# Power_1.net
KiCad netlist of a schematic drawn in Altium Designer
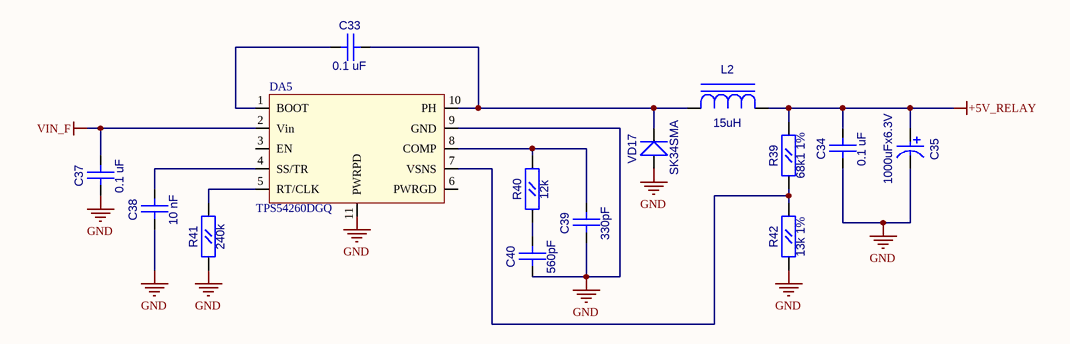
[diagram p0: Power_1.SchDoc]

(export (version "E")
  (design (tool "Eeschema 10.0.6"))
  (components
    (comp (ref "C33")
      (value "0.1 uF")
      (footprint "CC0603")
      (description "CC0603")
      (libsource (lib "gprs_modem_2") (part "CC0603"))
    )
    (comp (ref "C34")
      (value "0.1 uF")
      (footprint "CC0603")
      (description "CC0603")
      (libsource (lib "gprs_modem_2") (part "CC0603"))
    )
    (comp (ref "C35")
      (value "1000uFx6.3V")
      (footprint "CC8X3.5")
      (description "CAP0.35")
      (libsource (lib "gprs_modem_2") (part "CAP0.35"))
    )
    (comp (ref "C37")
      (value "0.1 uF")
      (footprint "CC0603")
      (description "CC0603")
      (libsource (lib "gprs_modem_2") (part "CC0603"))
    )
    (comp (ref "C38")
      (value "10 nF")
      (footprint "CC0603")
      (description "CC0603")
      (libsource (lib "gprs_modem_2") (part "CC0603"))
    )
    (comp (ref "C39")
      (value "330pF")
      (footprint "CC0603")
      (description "CC0603")
      (libsource (lib "gprs_modem_2") (part "CC0603"))
    )
    (comp (ref "C40")
      (value "560pF")
      (footprint "CC0603")
      (description "CC0603")
      (libsource (lib "gprs_modem_2") (part "CC0603"))
    )
    (comp (ref "DA5")
      (value "TPS54260DGQ")
      (footprint "S-PDSO-G10")
      (libsource (lib "gprs_modem_2") (part "TPS54260DGQ"))
    )
    (comp (ref "L2")
      (value "15uH")
      (footprint "SDR0805")
      (description "SDR0805")
      (libsource (lib "gprs_modem_2") (part "SDR0805"))
    )
    (comp (ref "R39")
      (value "68k1 1%")
      (footprint "RC0603")
      (description "RC0603")
      (libsource (lib "gprs_modem_2") (part "RC0603"))
    )
    (comp (ref "R40")
      (value "12k")
      (footprint "RC0603")
      (description "RC0603")
      (libsource (lib "gprs_modem_2") (part "RC0603"))
    )
    (comp (ref "R41")
      (value "240k")
      (footprint "RC0603")
      (description "RC0603")
      (libsource (lib "gprs_modem_2") (part "RC0603"))
    )
    (comp (ref "R42")
      (value "13k 1%")
      (footprint "RC0603")
      (description "RC0603")
      (libsource (lib "gprs_modem_2") (part "RC0603"))
    )
    (comp (ref "VD17")
      (value "SK34SMA")
      (footprint "SMA")
      (description "Schottky Rectifier")
      (libsource (lib "gprs_modem") (part "SK34SMA"))
    )
  )
  (nets
    (net (code "1") (name "+5V_RELAY") (class "Default")
      (node (ref "C34") (pin "1") (pinfunction "A_1") (pintype "passive"))
      (node (ref "C35") (pin "1") (pintype "passive"))
      (node (ref "L2") (pin "2") (pinfunction "A_2") (pintype "passive"))
      (node (ref "R39") (pin "2") (pinfunction "B_2") (pintype "passive"))
    )
    (net (code "2") (name "GND") (class "Default")
      (node (ref "C34") (pin "2") (pinfunction "B_2") (pintype "passive"))
      (node (ref "C35") (pin "2") (pintype "passive"))
      (node (ref "C37") (pin "2") (pinfunction "B_2") (pintype "passive"))
      (node (ref "C38") (pin "2") (pinfunction "B_2") (pintype "passive"))
      (node (ref "C39") (pin "2") (pinfunction "B_2") (pintype "passive"))
      (node (ref "C40") (pin "2") (pinfunction "B_2") (pintype "passive"))
      (node (ref "DA5") (pin "11") (pinfunction "PWRPD_11") (pintype "passive"))
      (node (ref "DA5") (pin "9") (pinfunction "GND_9") (pintype "passive"))
      (node (ref "R41") (pin "1") (pinfunction "A_1") (pintype "passive"))
      (node (ref "R42") (pin "1") (pinfunction "A_1") (pintype "passive"))
      (node (ref "VD17") (pin "1") (pinfunction "A_1") (pintype "passive"))
    )
    (net (code "3") (name "Net-(C33-A)") (class "Default")
      (node (ref "C33") (pin "1") (pinfunction "A_1") (pintype "passive"))
      (node (ref "DA5") (pin "10") (pinfunction "PH_10") (pintype "passive"))
      (node (ref "L2") (pin "1") (pinfunction "C_1") (pintype "passive"))
      (node (ref "VD17") (pin "2") (pinfunction "K_2") (pintype "passive"))
    )
    (net (code "4") (name "Net-(C33-B)") (class "Default")
      (node (ref "C33") (pin "2") (pinfunction "B_2") (pintype "passive"))
      (node (ref "DA5") (pin "1") (pinfunction "BOOT_1") (pintype "passive"))
    )
    (net (code "5") (name "Net-(C38-A)") (class "Default")
      (node (ref "C38") (pin "1") (pinfunction "A_1") (pintype "passive"))
      (node (ref "DA5") (pin "4") (pinfunction "SS/TR_4") (pintype "passive"))
    )
    (net (code "6") (name "Net-(C39-A)") (class "Default")
      (node (ref "C39") (pin "1") (pinfunction "A_1") (pintype "passive"))
      (node (ref "DA5") (pin "8") (pinfunction "COMP_8") (pintype "passive"))
      (node (ref "R40") (pin "2") (pinfunction "B_2") (pintype "passive"))
    )
    (net (code "7") (name "Net-(C40-A)") (class "Default")
      (node (ref "C40") (pin "1") (pinfunction "A_1") (pintype "passive"))
      (node (ref "R40") (pin "1") (pinfunction "A_1") (pintype "passive"))
    )
    (net (code "8") (name "Net-(DA5-RT{slash}CLK)") (class "Default")
      (node (ref "DA5") (pin "5") (pinfunction "RT/CLK_5") (pintype "passive"))
      (node (ref "R41") (pin "2") (pinfunction "B_2") (pintype "passive"))
    )
    (net (code "9") (name "Net-(DA5-VSNS)") (class "Default")
      (node (ref "DA5") (pin "7") (pinfunction "VSNS_7") (pintype "passive"))
      (node (ref "R39") (pin "1") (pinfunction "A_1") (pintype "passive"))
      (node (ref "R42") (pin "2") (pinfunction "B_2") (pintype "passive"))
    )
    (net (code "10") (name "VIN_F") (class "Default")
      (node (ref "C37") (pin "1") (pinfunction "A_1") (pintype "passive"))
      (node (ref "DA5") (pin "2") (pinfunction "Vin_2") (pintype "passive"))
    )
    (net (code "11") (name "unconnected-(DA5-EN-Pad3)") (class "Default")
      (node (ref "DA5") (pin "3") (pinfunction "EN_3") (pintype "passive"))
    )
    (net (code "12") (name "unconnected-(DA5-PWRGD-Pad6)") (class "Default")
      (node (ref "DA5") (pin "6") (pinfunction "PWRGD_6") (pintype "passive"))
    )
  )
)
